# SCH_Tanbre_v2_2026-05-30_3.net
KiCad netlist of a schematic drawn in EasyEDA
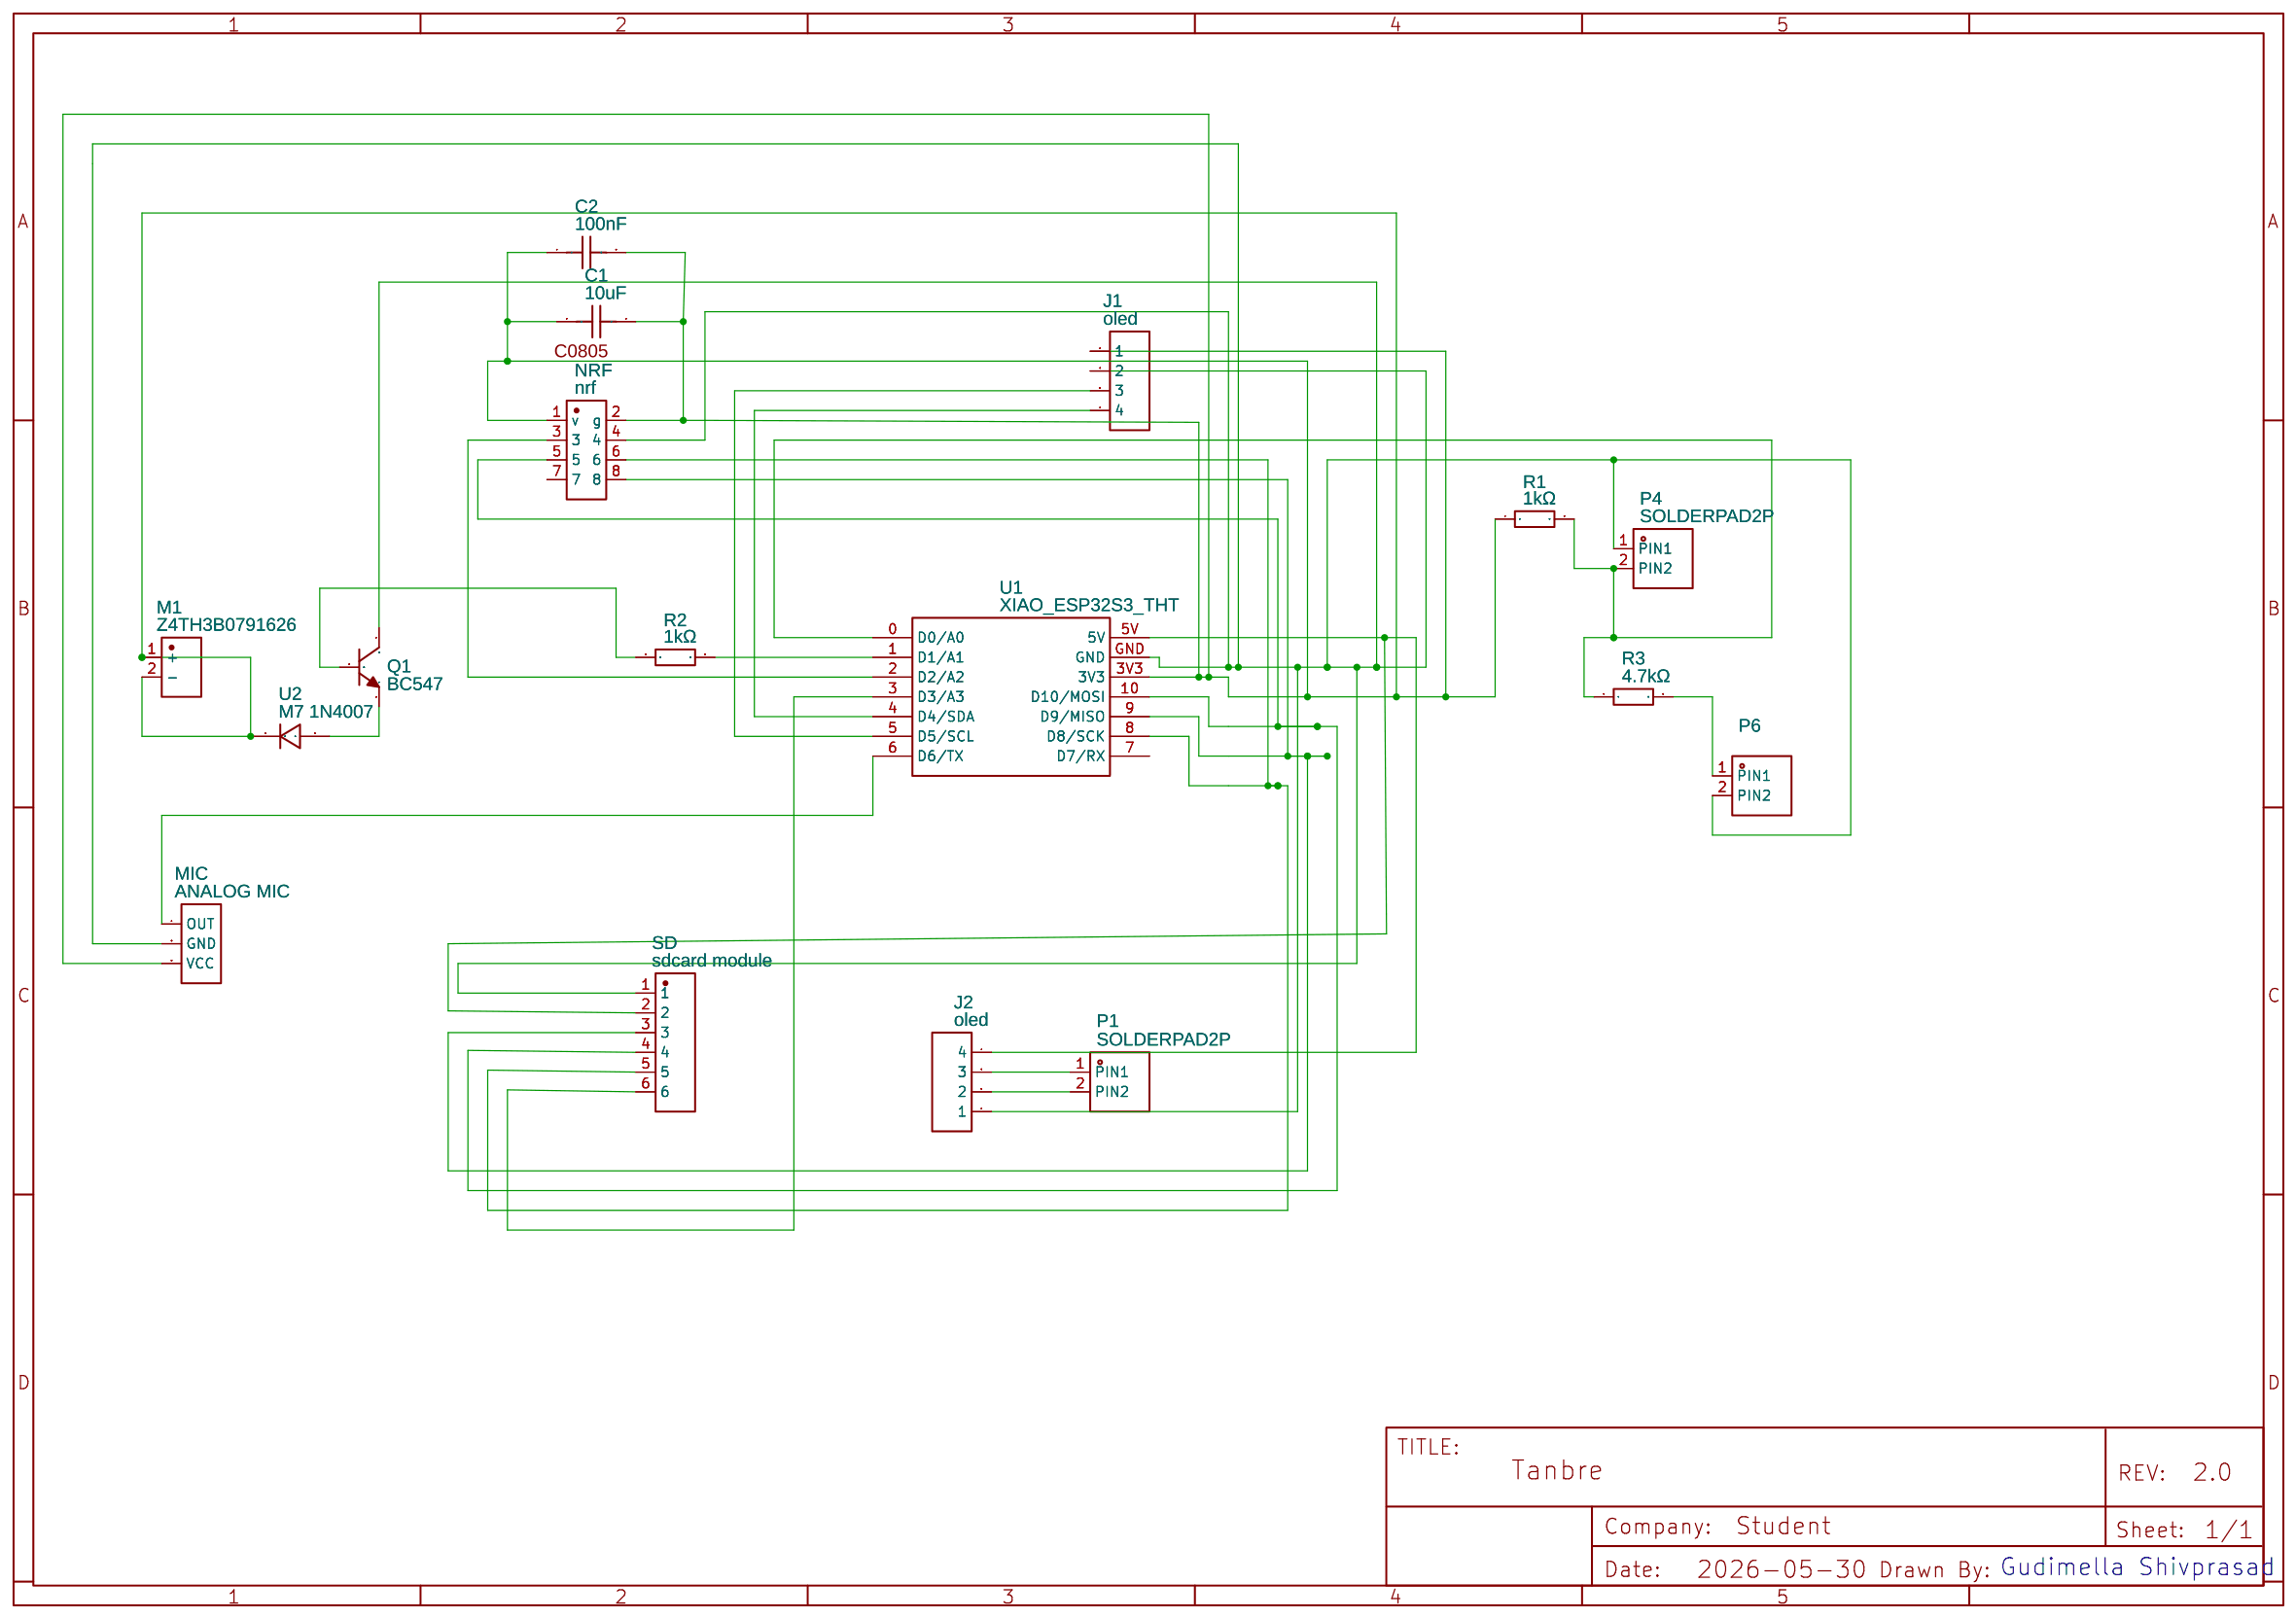
[diagram p0: schematic sheet]

(export (version "E")
  (design (tool "Eeschema 10.0.6"))
  (components
    (comp (ref "C1")
      (value "10uF")
      (fields
        (field (name "Manufacturer Part") "V106K0805X5R250NHP")
        (field (name "Manufacturer") "VIIYONG(微容)")
      )
      (libsource (lib "") (part "V106K0805X5R250NHP"))
    )
    (comp (ref "C2")
      (value "100nF")
      (fields
        (field (name "Manufacturer Part") "VJ0805Y104KXXCW1BC")
        (field (name "Manufacturer") "VISHAY(威世)")
      )
      (libsource (lib "") (part "VJ0805Y104KXXCW1BC"))
    )
    (comp (ref "J1") (value "oled") (libsource (lib "") (part "HDR-M-2.54_1x4_1")))
    (comp (ref "J2") (value "oled") (libsource (lib "") (part "HDR-M-2.54_1x4")))
    (comp (ref "M1")
      (value "Z4TH3B0791626")
      (fields (field (name "Manufacturer") "KOTL(金龙机电)"))
      (libsource (lib "") (part "Z4TH3B0791626"))
    )
    (comp (ref "MIC") (value "ANALOG MIC") (libsource (lib "") (part "HDR-M-2.54_1x3")))
    (comp (ref "NRF")
      (value "nrf")
      (fields (field (name "Manufacturer Part") "2X4 DIP"))
      (libsource (lib "") (part "2X4 DIP"))
    )
    (comp (ref "P1")
      (value "SOLDERPAD2P")
      (fields (field (name "Manufacturer Part") "New SchematicLib"))
      (libsource (lib "") (part "SOLDERPAD2P"))
    )
    (comp (ref "P4")
      (value "SOLDERPAD2P")
      (fields (field (name "Manufacturer Part") "New SchematicLib"))
      (libsource (lib "") (part "SOLDERPAD2P"))
    )
    (comp (ref "P6")
      (value "SOLDERPAD2P")
      (fields (field (name "Manufacturer Part") "New SchematicLib"))
      (libsource (lib "") (part "SOLDERPAD2P"))
    )
    (comp (ref "Q1")
      (value "BC547")
      (fields
        (field (name "Manufacturer Part") "BC547(RANGE:420-800)")
        (field (name "Manufacturer") "CJ(江苏长电/长晶)")
      )
      (libsource (lib "") (part "BC547"))
    )
    (comp (ref "R1")
      (value "1kΩ")
      (fields (field (name "Manufacturer Part") "CR-02JL6----1K") (field (name "Manufacturer") "Viking(光颉)"))
      (libsource (lib "") (part "CR-02JL6----1K"))
    )
    (comp (ref "R2")
      (value "1kΩ")
      (fields (field (name "Manufacturer Part") "CR-02JL6----1K") (field (name "Manufacturer") "Viking(光颉)"))
      (libsource (lib "") (part "CR-02JL6----1K"))
    )
    (comp (ref "R3")
      (value "4.7kΩ")
      (fields (field (name "Manufacturer Part") "RMC12064.7K5%N") (field (name "Manufacturer") "Tyohm(幸亚电阻)"))
      (libsource (lib "") (part "RMC12064.7K5%N"))
    )
    (comp (ref "SD")
      (value "sdcard module")
      (fields
        (field (name "Manufacturer Part") "HC-PM254-5.0H-1x6PZ")
        (field (name "Manufacturer") "HC(虹成电子)")
      )
      (libsource (lib "") (part "HC-PM254-5.0H-1X6PZ"))
    )
    (comp (ref "U1") (value "XIAO_ESP32S3_THT") (libsource (lib "") (part "XIAO_ESP32S3_THT")))
    (comp (ref "U2")
      (value "M7 1N4007")
      (fields (field (name "Manufacturer") "JUXING(钜兴)"))
      (libsource (lib "") (part "M7 1N4007"))
    )
  )
  (nets
    (net (code "1") (name "Net-(J2-Pad4)") (class "Default")
      (node (ref "J2") (pin "4") (pinfunction "4_4") (pintype "unspecified"))
      (node (ref "SD") (pin "2") (pinfunction "2_2") (pintype "unspecified"))
      (node (ref "U1") (pin "5V") (pinfunction "5V_5V") (pintype "unspecified"))
    )
    (net (code "2") (name "Net-(M1-+)") (class "Default")
      (node (ref "C1") (pin "1") (pinfunction "1_1") (pintype "unspecified"))
      (node (ref "C1") (pin "2") (pinfunction "2_2") (pintype "unspecified"))
      (node (ref "C2") (pin "1") (pinfunction "1_1") (pintype "unspecified"))
      (node (ref "C2") (pin "2") (pinfunction "2_2") (pintype "unspecified"))
      (node (ref "J1") (pin "1") (pinfunction "1_1") (pintype "unspecified"))
      (node (ref "J1") (pin "2") (pinfunction "2_2") (pintype "unspecified"))
      (node (ref "J2") (pin "1") (pinfunction "1_1") (pintype "unspecified"))
      (node (ref "M1") (pin "1") (pinfunction "+_1") (pintype "unspecified"))
      (node (ref "M1") (pin "2") (pinfunction "-_2") (pintype "unspecified"))
      (node (ref "MIC") (pin "2") (pinfunction "GND_2") (pintype "unspecified"))
      (node (ref "MIC") (pin "3") (pinfunction "VCC_3") (pintype "unspecified"))
      (node (ref "NRF") (pin "1") (pinfunction "v_1") (pintype "unspecified"))
      (node (ref "NRF") (pin "2") (pinfunction "g_2") (pintype "unspecified"))
      (node (ref "NRF") (pin "4") (pinfunction "4_4") (pintype "unspecified"))
      (node (ref "P4") (pin "1") (pinfunction "PIN1_1") (pintype "unspecified"))
      (node (ref "P6") (pin "2") (pinfunction "PIN2_2") (pintype "unspecified"))
      (node (ref "Q1") (pin "1") (pinfunction "C_1") (pintype "unspecified"))
      (node (ref "R1") (pin "1") (pinfunction "1_1") (pintype "unspecified"))
      (node (ref "SD") (pin "1") (pinfunction "1_1") (pintype "unspecified"))
      (node (ref "U1") (pin "3V3") (pinfunction "3V3_3V3") (pintype "unspecified"))
      (node (ref "U1") (pin "GND") (pinfunction "GND_GND") (pintype "unspecified"))
      (node (ref "U2") (pin "1") (pinfunction "1_1") (pintype "unspecified"))
    )
    (net (code "3") (name "Net-(MIC-OUT)") (class "Default")
      (node (ref "MIC") (pin "1") (pinfunction "OUT_1") (pintype "unspecified"))
      (node (ref "U1") (pin "6") (pinfunction "D6/TX_6") (pintype "unspecified"))
    )
    (net (code "4") (name "Net-(P1-PIN1)") (class "Default")
      (node (ref "J2") (pin "3") (pinfunction "3_3") (pintype "unspecified"))
      (node (ref "P1") (pin "1") (pinfunction "PIN1_1") (pintype "unspecified"))
    )
    (net (code "5") (name "Net-(P1-PIN2)") (class "Default")
      (node (ref "J2") (pin "2") (pinfunction "2_2") (pintype "unspecified"))
      (node (ref "P1") (pin "2") (pinfunction "PIN2_2") (pintype "unspecified"))
    )
    (net (code "6") (name "Net-(P4-PIN2)") (class "Default")
      (node (ref "P4") (pin "2") (pinfunction "PIN2_2") (pintype "unspecified"))
      (node (ref "R1") (pin "2") (pinfunction "2_2") (pintype "unspecified"))
      (node (ref "R3") (pin "1") (pinfunction "1_1") (pintype "unspecified"))
      (node (ref "U1") (pin "0") (pinfunction "D0/A0_0") (pintype "unspecified"))
    )
    (net (code "7") (name "Net-(P6-PIN1)") (class "Default")
      (node (ref "P6") (pin "1") (pinfunction "PIN1_1") (pintype "unspecified"))
      (node (ref "R3") (pin "2") (pinfunction "2_2") (pintype "unspecified"))
    )
    (net (code "8") (name "Net-(Q1-B)") (class "Default")
      (node (ref "Q1") (pin "2") (pinfunction "B_2") (pintype "unspecified"))
      (node (ref "R2") (pin "1") (pinfunction "1_1") (pintype "unspecified"))
    )
    (net (code "9") (name "Net-(Q1-E)") (class "Default")
      (node (ref "Q1") (pin "3") (pinfunction "E_3") (pintype "unspecified"))
      (node (ref "U2") (pin "2") (pinfunction "2_2") (pintype "unspecified"))
    )
    (net (code "10") (name "Net-(U1-D1{slash}A1)") (class "Default")
      (node (ref "R2") (pin "2") (pinfunction "2_2") (pintype "unspecified"))
      (node (ref "U1") (pin "1") (pinfunction "D1/A1_1") (pintype "unspecified"))
    )
    (net (code "11") (name "Net-(U1-D2{slash}A2)") (class "Default")
      (node (ref "NRF") (pin "3") (pinfunction "3_3") (pintype "unspecified"))
      (node (ref "U1") (pin "2") (pinfunction "D2/A2_2") (pintype "unspecified"))
    )
    (net (code "12") (name "Net-(U1-D3{slash}A3)") (class "Default")
      (node (ref "SD") (pin "6") (pinfunction "6_6") (pintype "unspecified"))
      (node (ref "U1") (pin "3") (pinfunction "D3/A3_3") (pintype "unspecified"))
    )
    (net (code "13") (name "Net-(U1-D4{slash}SDA)") (class "Default")
      (node (ref "J1") (pin "4") (pinfunction "4_4") (pintype "unspecified"))
      (node (ref "U1") (pin "4") (pinfunction "D4/SDA_4") (pintype "unspecified"))
    )
    (net (code "14") (name "Net-(U1-D5{slash}SCL)") (class "Default")
      (node (ref "J1") (pin "3") (pinfunction "3_3") (pintype "unspecified"))
      (node (ref "U1") (pin "5") (pinfunction "D5/SCL_5") (pintype "unspecified"))
    )
    (net (code "15") (name "Net-(U1-D8{slash}SCK)") (class "Default")
      (node (ref "NRF") (pin "6") (pinfunction "6_6") (pintype "unspecified"))
      (node (ref "SD") (pin "5") (pinfunction "5_5") (pintype "unspecified"))
      (node (ref "U1") (pin "8") (pinfunction "D8/SCK_8") (pintype "unspecified"))
    )
    (net (code "16") (name "Net-(U1-D9{slash}MISO)") (class "Default")
      (node (ref "NRF") (pin "8") (pinfunction "8_8") (pintype "unspecified"))
      (node (ref "SD") (pin "3") (pinfunction "3_3") (pintype "unspecified"))
      (node (ref "U1") (pin "9") (pinfunction "D9/MISO_9") (pintype "unspecified"))
    )
    (net (code "17") (name "Net-(U1-D10{slash}MOSI)") (class "Default")
      (node (ref "NRF") (pin "5") (pinfunction "5_5") (pintype "unspecified"))
      (node (ref "SD") (pin "4") (pinfunction "4_4") (pintype "unspecified"))
      (node (ref "U1") (pin "10") (pinfunction "D10/MOSI_10") (pintype "unspecified"))
    )
    (net (code "18") (name "unconnected-(NRF-Pad7)") (class "Default")
      (node (ref "NRF") (pin "7") (pinfunction "7_7") (pintype "unspecified"))
    )
    (net (code "19") (name "unconnected-(U1-D7{slash}RX-Pad7)") (class "Default")
      (node (ref "U1") (pin "7") (pinfunction "D7/RX_7") (pintype "unspecified"))
    )
  )
)
